# sensor_board.net
KiCad netlist of a schematic drawn in EAGLE
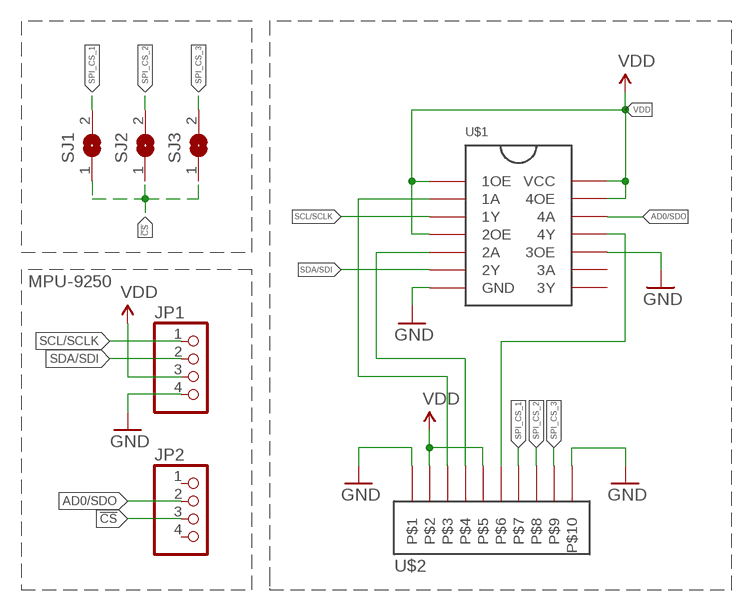
[diagram p0: schematic, sheet 1]

(export (version "E")
  (design (tool "Eeschema 10.0.6"))
  (components
    (comp (ref "JP1")
      (value "PINHD-1X04_2.54-SMD")
      (footprint "eagle-import:1X04SMD")
      (libsource (lib "eagle-import") (part "PINHD-1X04_2.54-SMD"))
    )
    (comp (ref "JP2")
      (value "PINHD-1X04_2.54-SMD")
      (footprint "eagle-import:1X04SMD")
      (libsource (lib "eagle-import") (part "PINHD-1X04_2.54-SMD"))
    )
    (comp (ref "SJ1") (value "SJ") (footprint "eagle-import:SJ") (libsource (lib "eagle-import") (part "SJ")))
    (comp (ref "SJ2") (value "SJ") (footprint "eagle-import:SJ") (libsource (lib "eagle-import") (part "SJ")))
    (comp (ref "SJ3") (value "SJ") (footprint "eagle-import:SJ") (libsource (lib "eagle-import") (part "SJ")))
    (comp (ref "U$1")
      (value "74AHC126D,118")
      (footprint "eagle-import:SOIC127P600X175-14N")
      (libsource (lib "eagle-import") (part "74AHC126D,118"))
    )
    (comp (ref "U$2")
      (value "1-2178711-2")
      (footprint "eagle-import:1-2178712-0")
      (libsource (lib "eagle-import") (part "1-2178711-2"))
    )
  )
  (nets
    (net (code "1") (name "/~{CS}") (class "Default")
      (node (ref "JP2") (pin "3") (pinfunction "3_3") (pintype "passive"))
      (node (ref "SJ1") (pin "1") (pinfunction "1_1") (pintype "passive"))
      (node (ref "SJ2") (pin "1") (pinfunction "1_1") (pintype "passive"))
      (node (ref "SJ3") (pin "1") (pinfunction "1_1") (pintype "passive"))
    )
    (net (code "2") (name "AD0{slash}SDO") (class "Default")
      (node (ref "JP2") (pin "2") (pinfunction "2_2") (pintype "passive"))
      (node (ref "U$1") (pin "12") (pinfunction "4A_12") (pintype "bidirectional"))
    )
    (net (code "3") (name "GND") (class "Default")
      (node (ref "JP1") (pin "4") (pinfunction "4_4") (pintype "passive"))
      (node (ref "U$1") (pin "10") (pinfunction "3OE_10") (pintype "bidirectional"))
      (node (ref "U$1") (pin "7") (pinfunction "GND_7") (pintype "bidirectional"))
      (node (ref "U$2") (pin "P$1") (pinfunction "P$1_P$1") (pintype "bidirectional"))
      (node (ref "U$2") (pin "P$10") (pinfunction "P$10_P$10") (pintype "bidirectional"))
    )
    (net (code "4") (name "Net-(U$1-1A)") (class "Default")
      (node (ref "U$1") (pin "2") (pinfunction "1A_2") (pintype "bidirectional"))
      (node (ref "U$2") (pin "P$3") (pinfunction "P$3_P$3") (pintype "bidirectional"))
    )
    (net (code "5") (name "Net-(U$1-2A)") (class "Default")
      (node (ref "U$1") (pin "5") (pinfunction "2A_5") (pintype "bidirectional"))
      (node (ref "U$2") (pin "P$4") (pinfunction "P$4_P$4") (pintype "bidirectional"))
    )
    (net (code "6") (name "Net-(U$1-4Y)") (class "Default")
      (node (ref "U$1") (pin "11") (pinfunction "4Y_11") (pintype "bidirectional"))
      (node (ref "U$2") (pin "P$6") (pinfunction "P$6_P$6") (pintype "bidirectional"))
    )
    (net (code "7") (name "SCL{slash}SCLK") (class "Default")
      (node (ref "JP1") (pin "1") (pinfunction "1_1") (pintype "passive"))
      (node (ref "U$1") (pin "3") (pinfunction "1Y_3") (pintype "bidirectional"))
    )
    (net (code "8") (name "SDA{slash}SDI") (class "Default")
      (node (ref "JP1") (pin "2") (pinfunction "2_2") (pintype "passive"))
      (node (ref "U$1") (pin "6") (pinfunction "2Y_6") (pintype "bidirectional"))
    )
    (net (code "9") (name "SPI_CS_1") (class "Default")
      (node (ref "SJ1") (pin "2") (pinfunction "2_2") (pintype "passive"))
      (node (ref "U$2") (pin "P$7") (pinfunction "P$7_P$7") (pintype "bidirectional"))
    )
    (net (code "10") (name "SPI_CS_2") (class "Default")
      (node (ref "SJ2") (pin "2") (pinfunction "2_2") (pintype "passive"))
      (node (ref "U$2") (pin "P$8") (pinfunction "P$8_P$8") (pintype "bidirectional"))
    )
    (net (code "11") (name "SPI_CS_3") (class "Default")
      (node (ref "SJ3") (pin "2") (pinfunction "2_2") (pintype "passive"))
      (node (ref "U$2") (pin "P$9") (pinfunction "P$9_P$9") (pintype "bidirectional"))
    )
    (net (code "12") (name "VDD") (class "Default")
      (node (ref "JP1") (pin "3") (pinfunction "3_3") (pintype "passive"))
      (node (ref "U$1") (pin "1") (pinfunction "1OE_1") (pintype "bidirectional"))
      (node (ref "U$1") (pin "13") (pinfunction "4OE_13") (pintype "bidirectional"))
      (node (ref "U$1") (pin "14") (pinfunction "VCC_14") (pintype "bidirectional"))
      (node (ref "U$1") (pin "4") (pinfunction "2OE_4") (pintype "bidirectional"))
      (node (ref "U$2") (pin "P$2") (pinfunction "P$2_P$2") (pintype "bidirectional"))
      (node (ref "U$2") (pin "P$5") (pinfunction "P$5_P$5") (pintype "bidirectional"))
    )
    (net (code "13") (name "unconnected-(JP2-Pad1)") (class "Default")
      (node (ref "JP2") (pin "1") (pinfunction "1_1") (pintype "passive"))
    )
    (net (code "14") (name "unconnected-(JP2-Pad4)") (class "Default")
      (node (ref "JP2") (pin "4") (pinfunction "4_4") (pintype "passive"))
    )
    (net (code "15") (name "unconnected-(U$1-3A-Pad9)") (class "Default")
      (node (ref "U$1") (pin "9") (pinfunction "3A_9") (pintype "bidirectional"))
    )
    (net (code "16") (name "unconnected-(U$1-3Y-Pad8)") (class "Default")
      (node (ref "U$1") (pin "8") (pinfunction "3Y_8") (pintype "bidirectional"))
    )
  )
)
